# brain.net
KiCad netlist of a schematic drawn in EAGLE
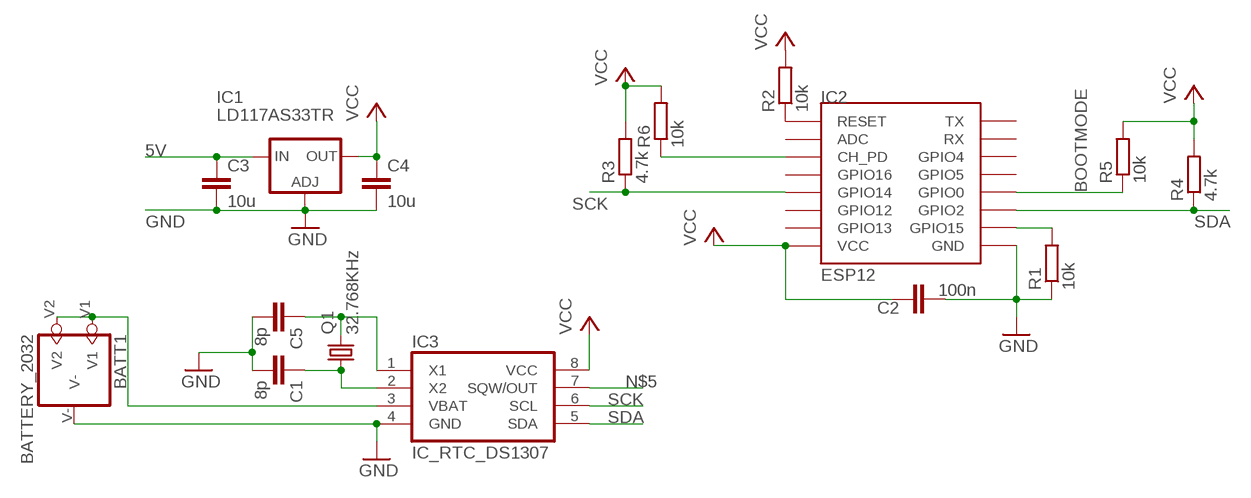
[diagram p0: schematic, sheet 1]

(export (version "E")
  (design (tool "Eeschema 10.0.6"))
  (components
    (comp (ref "BATT1")
      (value "BATTERY_2032")
      (footprint "eagle-import:BATT2032")
      (libsource (lib "eagle-import") (part "BATTERY_2032"))
    )
    (comp (ref "C1")
      (value "8p")
      (footprint "eagle-import:C0805")
      (libsource (lib "eagle-import") (part "C-EUC0805"))
    )
    (comp (ref "C2")
      (value "100n")
      (footprint "eagle-import:C0805")
      (libsource (lib "eagle-import") (part "C-EUC0805"))
    )
    (comp (ref "C3")
      (value "10u")
      (footprint "eagle-import:C0805")
      (libsource (lib "eagle-import") (part "C-EUC0805"))
    )
    (comp (ref "C4")
      (value "10u")
      (footprint "eagle-import:C0805")
      (libsource (lib "eagle-import") (part "C-EUC0805"))
    )
    (comp (ref "C5")
      (value "8p")
      (footprint "eagle-import:C0805")
      (libsource (lib "eagle-import") (part "C-EUC0805"))
    )
    (comp (ref "IC1")
      (value "LD117AS33TR")
      (footprint "eagle-import:SOT223")
      (libsource (lib "eagle-import") (part "LD117A?S33TR"))
    )
    (comp (ref "IC2")
      (value "ESP12")
      (footprint "eagle-import:ESP12")
      (libsource (lib "eagle-import") (part "ESP12"))
    )
    (comp (ref "IC3")
      (value "IC_RTC_DS1307")
      (footprint "eagle-import:SO-8")
      (libsource (lib "eagle-import") (part "IC_RTC_DS1307"))
    )
    (comp (ref "Q1")
      (value "32.768KHz")
      (footprint "eagle-import:TC26H")
      (libsource (lib "eagle-import") (part "CRYSTALTC26H"))
    )
    (comp (ref "R1")
      (value "10k")
      (footprint "eagle-import:R0805")
      (libsource (lib "eagle-import") (part "R-EU_R0805"))
    )
    (comp (ref "R2")
      (value "10k")
      (footprint "eagle-import:R0805")
      (libsource (lib "eagle-import") (part "R-EU_R0805"))
    )
    (comp (ref "R3")
      (value "4.7k")
      (footprint "eagle-import:R0805")
      (libsource (lib "eagle-import") (part "R-EU_R0805"))
    )
    (comp (ref "R4")
      (value "4.7k")
      (footprint "eagle-import:R0805")
      (libsource (lib "eagle-import") (part "R-EU_R0805"))
    )
    (comp (ref "R5")
      (value "10k")
      (footprint "eagle-import:R0805")
      (libsource (lib "eagle-import") (part "R-EU_R0805"))
    )
    (comp (ref "R6")
      (value "10k")
      (footprint "eagle-import:R0805")
      (libsource (lib "eagle-import") (part "R-EU_R0805"))
    )
  )
  (nets
    (net (code "1") (name "/5V") (class "Default")
      (node (ref "C3") (pin "1") (pinfunction "1_1") (pintype "passive"))
      (node (ref "IC1") (pin "3") (pinfunction "IN_3") (pintype "input"))
    )
    (net (code "2") (name "/BOOTMODE") (class "Default")
      (node (ref "IC2") (pin "GPIO0") (pinfunction "GPIO0_GPIO0") (pintype "bidirectional"))
      (node (ref "R5") (pin "1") (pinfunction "1_1") (pintype "passive"))
    )
    (net (code "3") (name "/N$5") (class "Default")
      (node (ref "IC3") (pin "7") (pinfunction "SQW/OUT_7") (pintype "bidirectional"))
    )
    (net (code "4") (name "/SCK") (class "Default")
      (node (ref "IC2") (pin "GPIO14") (pinfunction "GPIO14_GPIO14") (pintype "bidirectional"))
      (node (ref "IC3") (pin "6") (pinfunction "SCL_6") (pintype "bidirectional"))
      (node (ref "R3") (pin "1") (pinfunction "1_1") (pintype "passive"))
    )
    (net (code "5") (name "/SDA") (class "Default")
      (node (ref "IC2") (pin "GPIO2") (pinfunction "GPIO2_GPIO2") (pintype "bidirectional"))
      (node (ref "IC3") (pin "5") (pinfunction "SDA_5") (pintype "bidirectional"))
      (node (ref "R4") (pin "1") (pinfunction "1_1") (pintype "passive"))
    )
    (net (code "6") (name "GND") (class "Default")
      (node (ref "BATT1") (pin "V-") (pinfunction "V-_V-") (pintype "power_in"))
      (node (ref "C1") (pin "2") (pinfunction "2_2") (pintype "passive"))
      (node (ref "C2") (pin "2") (pinfunction "2_2") (pintype "passive"))
      (node (ref "C3") (pin "2") (pinfunction "2_2") (pintype "passive"))
      (node (ref "C4") (pin "2") (pinfunction "2_2") (pintype "passive"))
      (node (ref "C5") (pin "2") (pinfunction "2_2") (pintype "passive"))
      (node (ref "IC1") (pin "1") (pinfunction "ADJ_1") (pintype "input"))
      (node (ref "IC2") (pin "GND") (pinfunction "GND_GND") (pintype "bidirectional"))
      (node (ref "IC3") (pin "4") (pinfunction "GND_4") (pintype "bidirectional"))
      (node (ref "R1") (pin "1") (pinfunction "1_1") (pintype "passive"))
    )
    (net (code "7") (name "Net-(IC2-PadCH_PD)") (class "Default")
      (node (ref "IC2") (pin "CH_PD") (pinfunction "CH_PD_CH_PD") (pintype "bidirectional"))
      (node (ref "R6") (pin "1") (pinfunction "1_1") (pintype "passive"))
    )
    (net (code "8") (name "Net-(IC2-PadGPIO15)") (class "Default")
      (node (ref "IC2") (pin "GPIO15") (pinfunction "GPIO15_GPIO15") (pintype "bidirectional"))
      (node (ref "R1") (pin "2") (pinfunction "2_2") (pintype "passive"))
    )
    (net (code "9") (name "Net-(IC2-PadRESET)") (class "Default")
      (node (ref "IC2") (pin "RESET") (pinfunction "RESET_RESET") (pintype "bidirectional"))
      (node (ref "R2") (pin "1") (pinfunction "1_1") (pintype "passive"))
    )
    (net (code "10") (name "Net-(IC3-VBAT)") (class "Default")
      (node (ref "BATT1") (pin "V1") (pinfunction "V1_V1") (pintype "power_in"))
      (node (ref "BATT1") (pin "V2") (pinfunction "V2_V2") (pintype "power_in"))
      (node (ref "IC3") (pin "3") (pinfunction "VBAT_3") (pintype "bidirectional"))
    )
    (net (code "11") (name "Net-(IC3-X1)") (class "Default")
      (node (ref "C5") (pin "1") (pinfunction "1_1") (pintype "passive"))
      (node (ref "IC3") (pin "1") (pinfunction "X1_1") (pintype "bidirectional"))
      (node (ref "Q1") (pin "2") (pinfunction "2_2") (pintype "passive"))
    )
    (net (code "12") (name "Net-(IC3-X2)") (class "Default")
      (node (ref "C1") (pin "1") (pinfunction "1_1") (pintype "passive"))
      (node (ref "IC3") (pin "2") (pinfunction "X2_2") (pintype "bidirectional"))
      (node (ref "Q1") (pin "1") (pinfunction "1_1") (pintype "passive"))
    )
    (net (code "13") (name "VCC") (class "Default")
      (node (ref "C2") (pin "1") (pinfunction "1_1") (pintype "passive"))
      (node (ref "C4") (pin "1") (pinfunction "1_1") (pintype "passive"))
      (node (ref "IC1") (pin "4") (pinfunction "OUT_4") (pintype "passive"))
      (node (ref "IC2") (pin "VCC") (pinfunction "VCC_VCC") (pintype "bidirectional"))
      (node (ref "IC3") (pin "8") (pinfunction "VCC_8") (pintype "bidirectional"))
      (node (ref "R2") (pin "2") (pinfunction "2_2") (pintype "passive"))
      (node (ref "R3") (pin "2") (pinfunction "2_2") (pintype "passive"))
      (node (ref "R4") (pin "2") (pinfunction "2_2") (pintype "passive"))
      (node (ref "R5") (pin "2") (pinfunction "2_2") (pintype "passive"))
      (node (ref "R6") (pin "2") (pinfunction "2_2") (pintype "passive"))
    )
    (net (code "14") (name "unconnected-(IC2-PadADC)") (class "Default")
      (node (ref "IC2") (pin "ADC") (pinfunction "ADC_ADC") (pintype "bidirectional"))
    )
    (net (code "15") (name "unconnected-(IC2-PadGPIO4)") (class "Default")
      (node (ref "IC2") (pin "GPIO4") (pinfunction "GPIO4_GPIO4") (pintype "bidirectional"))
    )
    (net (code "16") (name "unconnected-(IC2-PadGPIO5)") (class "Default")
      (node (ref "IC2") (pin "GPIO5") (pinfunction "GPIO5_GPIO5") (pintype "bidirectional"))
    )
    (net (code "17") (name "unconnected-(IC2-PadGPIO12)") (class "Default")
      (node (ref "IC2") (pin "GPIO12") (pinfunction "GPIO12_GPIO12") (pintype "bidirectional"))
    )
    (net (code "18") (name "unconnected-(IC2-PadGPIO13)") (class "Default")
      (node (ref "IC2") (pin "GPIO13") (pinfunction "GPIO13_GPIO13") (pintype "bidirectional"))
    )
    (net (code "19") (name "unconnected-(IC2-PadGPIO16)") (class "Default")
      (node (ref "IC2") (pin "GPIO16") (pinfunction "GPIO16_GPIO16") (pintype "bidirectional"))
    )
    (net (code "20") (name "unconnected-(IC2-PadRX)") (class "Default")
      (node (ref "IC2") (pin "RX") (pinfunction "RX_RX") (pintype "bidirectional"))
    )
    (net (code "21") (name "unconnected-(IC2-PadTX)") (class "Default")
      (node (ref "IC2") (pin "TX") (pinfunction "TX_TX") (pintype "bidirectional"))
    )
  )
)
